# LED_Driver.net
KiCad netlist of a schematic drawn in Altium Designer
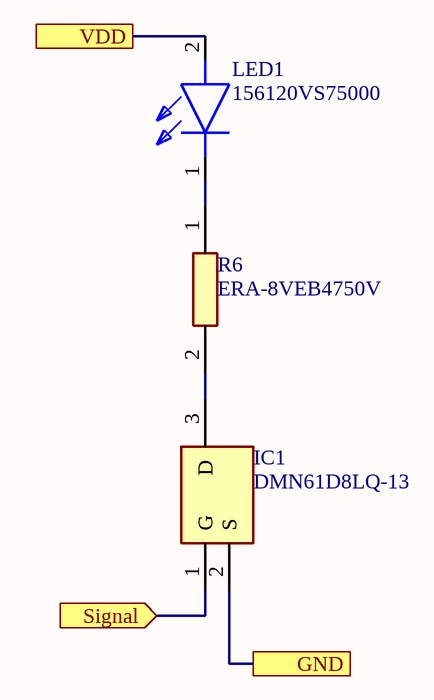
[diagram p0: LED_Driver.SchDoc]

(export (version "E")
  (design (tool "Eeschema 10.0.6"))
  (components
    (comp (ref "IC1")
      (value "DMN61D8LQ-13")
      (footprint "SamacSys:SOT96P240X110-3N")
      (description "Integrated Circuit")
      (fields (field (name "MOUSER PART NUMBER") "621-DMN61D8LQ-13"))
      (libsource (lib "*") (part "DMN61D8LQ-13"))
    )
    (comp (ref "LED1")
      (value "156120VS75000")
      (footprint "SamacSys:156120VS75000")
      (description "LED")
      (fields (field (name "MOUSER PART NUMBER") "710-156120VS75000"))
      (libsource (lib "*") (part "156120VS75000"))
    )
    (comp (ref "R6")
      (value "ERA-8VEB4750V")
      (footprint "SamacSys:ERA8KEB1004V")
      (description "475 ohm resistor")
      (fields (field (name "MOUSER PART NUMBER") "667-ERA-8VEB4750V"))
      (libsource (lib "*") (part "ERA-8VEB4750V"))
    )
  )
  (nets
    (net (code "1") (name "/GND") (class "Default")
      (node (ref "IC1") (pin "2") (pinfunction "S_2") (pintype "passive"))
    )
    (net (code "2") (name "/Signal") (class "Default")
      (node (ref "IC1") (pin "1") (pinfunction "G_1") (pintype "passive"))
    )
    (net (code "3") (name "/VDD") (class "Default")
      (node (ref "LED1") (pin "2") (pinfunction "A_2") (pintype "passive"))
    )
    (net (code "4") (name "Net-(IC1-D)") (class "Default")
      (node (ref "IC1") (pin "3") (pinfunction "D_3") (pintype "passive"))
      (node (ref "R6") (pin "2") (pinfunction "2_2") (pintype "passive"))
    )
    (net (code "5") (name "Net-(LED1-K)") (class "Default")
      (node (ref "LED1") (pin "1") (pinfunction "K_1") (pintype "passive"))
      (node (ref "R6") (pin "1") (pinfunction "1_1") (pintype "passive"))
    )
  )
)
